# RPi-Display_v10.net
KiCad netlist of a schematic drawn in EAGLE
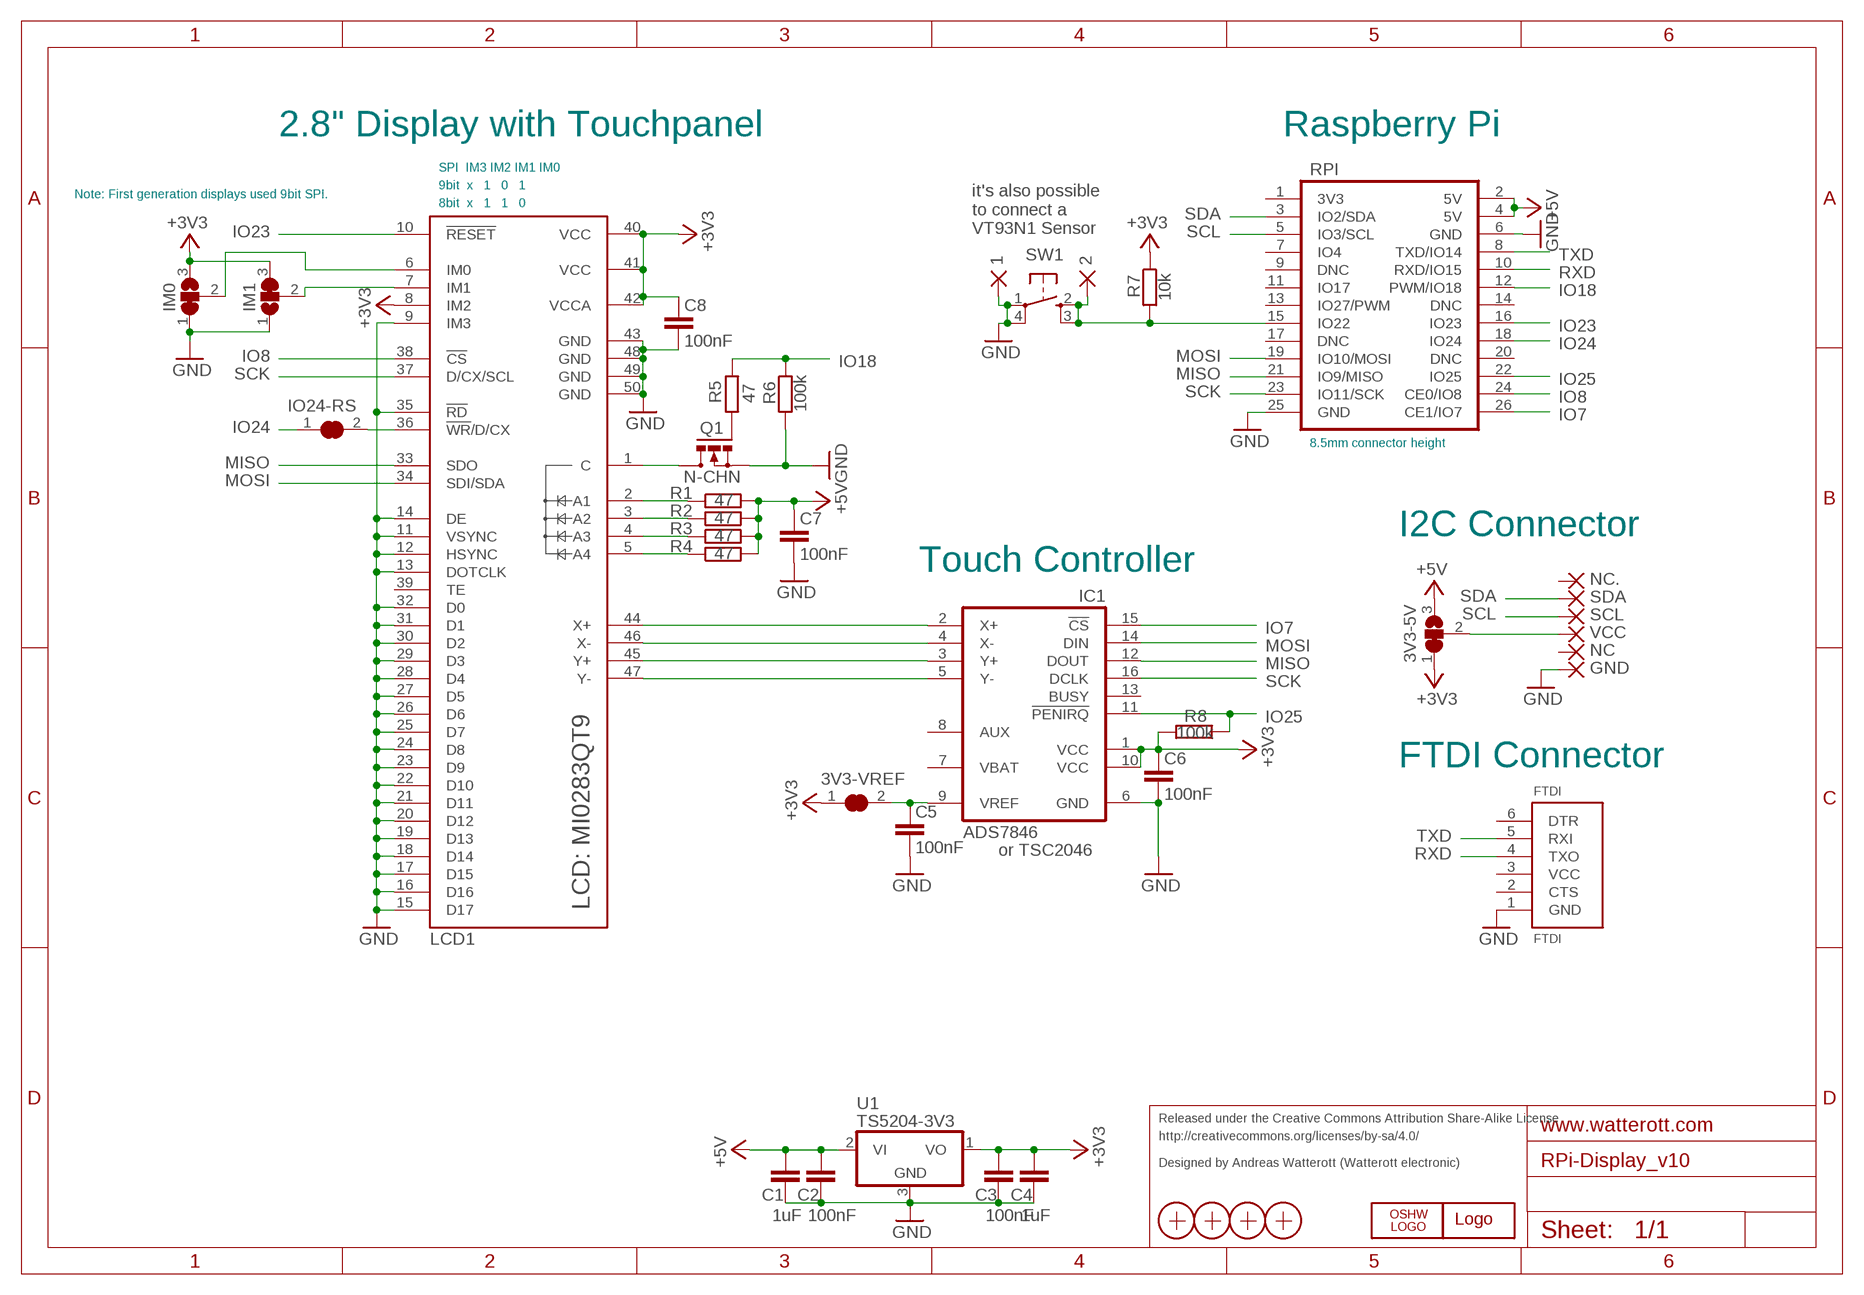
[diagram p0: schematic, sheet 1]

(export (version "E")
  (design (tool "Eeschema 10.0.6"))
  (components
    (comp (ref "1")
      (value "WIREPADSMD1,27-254")
      (footprint "eagle-import:SMD1,27-2,54")
      (libsource (lib "eagle-import") (part "WIREPADSMD1,27-254"))
    )
    (comp (ref "2")
      (value "WIREPADSMD1,27-254")
      (footprint "eagle-import:SMD1,27-2,54")
      (libsource (lib "eagle-import") (part "WIREPADSMD1,27-254"))
    )
    (comp (ref "3V3-5V")
      (value "SJ2W")
      (footprint "eagle-import:SJ_2")
      (libsource (lib "eagle-import") (part "SJ2W"))
    )
    (comp (ref "3V3-VREF")
      (value "SJ")
      (footprint "eagle-import:SJ")
      (libsource (lib "eagle-import") (part "SJ"))
    )
    (comp (ref "C1")
      (value "1uF")
      (footprint "eagle-import:C0603")
      (libsource (lib "eagle-import") (part "C-EUC0603"))
    )
    (comp (ref "C2")
      (value "100nF")
      (footprint "eagle-import:C0603")
      (libsource (lib "eagle-import") (part "C-EUC0603"))
    )
    (comp (ref "C3")
      (value "100nF")
      (footprint "eagle-import:C0603")
      (libsource (lib "eagle-import") (part "C-EUC0603"))
    )
    (comp (ref "C4")
      (value "1uF")
      (footprint "eagle-import:C0603")
      (libsource (lib "eagle-import") (part "C-EUC0603"))
    )
    (comp (ref "C5")
      (value "100nF")
      (footprint "eagle-import:C0603")
      (libsource (lib "eagle-import") (part "C-EUC0603"))
    )
    (comp (ref "C6")
      (value "100nF")
      (footprint "eagle-import:C0603")
      (libsource (lib "eagle-import") (part "C-EUC0603"))
    )
    (comp (ref "C7")
      (value "100nF")
      (footprint "eagle-import:C0603")
      (libsource (lib "eagle-import") (part "C-EUC0603"))
    )
    (comp (ref "C8")
      (value "100nF")
      (footprint "eagle-import:C0603")
      (libsource (lib "eagle-import") (part "C-EUC0603"))
    )
    (comp (ref "FTDI")
      (value "FTDI")
      (footprint "eagle-import:FTDI")
      (libsource (lib "eagle-import") (part "FTDI"))
    )
    (comp (ref "GND")
      (value "WIREPADSMD1,27-254")
      (footprint "eagle-import:SMD1,27-2,54")
      (libsource (lib "eagle-import") (part "WIREPADSMD1,27-254"))
    )
    (comp (ref "IC1")
      (value "ADS7846")
      (footprint "eagle-import:SSOP16")
      (libsource (lib "eagle-import") (part "ADS7846"))
    )
    (comp (ref "IM0")
      (value "SJ2W")
      (footprint "eagle-import:SJ_2")
      (libsource (lib "eagle-import") (part "SJ2W"))
    )
    (comp (ref "IM1")
      (value "SJ2W")
      (footprint "eagle-import:SJ_2")
      (libsource (lib "eagle-import") (part "SJ2W"))
    )
    (comp (ref "IO24-RS")
      (value "SJ")
      (footprint "eagle-import:SJ")
      (libsource (lib "eagle-import") (part "SJ"))
    )
    (comp (ref "LCD1")
      (value "MI0283QT9")
      (footprint "eagle-import:MI0283QT9")
      (libsource (lib "eagle-import") (part "MI0283QT9"))
    )
    (comp (ref "LOGO1")
      (value "OSHW_LOGO_6MILX0150-NT")
      (footprint "eagle-import:OSHW_6X150_NOTEXT")
      (libsource (lib "eagle-import") (part "OSHW_LOGO_6MILX0150-NT"))
    )
    (comp (ref "NC")
      (value "WIREPADSMD1,27-254")
      (footprint "eagle-import:SMD1,27-2,54")
      (libsource (lib "eagle-import") (part "WIREPADSMD1,27-254"))
    )
    (comp (ref "NC.")
      (value "WIREPADSMD1,27-254")
      (footprint "eagle-import:SMD1,27-2,54")
      (libsource (lib "eagle-import") (part "WIREPADSMD1,27-254"))
    )
    (comp (ref "Q1")
      (value "N-CHN")
      (footprint "eagle-import:MICRO3")
      (libsource (lib "eagle-import") (part "IRLML2502"))
    )
    (comp (ref "R1")
      (value "47")
      (footprint "eagle-import:R0603")
      (libsource (lib "eagle-import") (part "R-EU_R0603"))
    )
    (comp (ref "R2")
      (value "47")
      (footprint "eagle-import:R0603")
      (libsource (lib "eagle-import") (part "R-EU_R0603"))
    )
    (comp (ref "R3")
      (value "47")
      (footprint "eagle-import:R0603")
      (libsource (lib "eagle-import") (part "R-EU_R0603"))
    )
    (comp (ref "R4")
      (value "47")
      (footprint "eagle-import:R0603")
      (libsource (lib "eagle-import") (part "R-EU_R0603"))
    )
    (comp (ref "R5")
      (value "47")
      (footprint "eagle-import:R0603")
      (libsource (lib "eagle-import") (part "R-EU_R0603"))
    )
    (comp (ref "R6")
      (value "100k")
      (footprint "eagle-import:R0603")
      (libsource (lib "eagle-import") (part "R-EU_R0603"))
    )
    (comp (ref "R7")
      (value "10k")
      (footprint "eagle-import:R0603")
      (libsource (lib "eagle-import") (part "R-EU_R0603"))
    )
    (comp (ref "R8")
      (value "100k")
      (footprint "eagle-import:R0603")
      (libsource (lib "eagle-import") (part "R-EU_R0603"))
    )
    (comp (ref "RPI")
      (value "RPI")
      (footprint "eagle-import:RPI")
      (libsource (lib "eagle-import") (part "RPI"))
    )
    (comp (ref "SCL")
      (value "WIREPADSMD1,27-254")
      (footprint "eagle-import:SMD1,27-2,54")
      (libsource (lib "eagle-import") (part "WIREPADSMD1,27-254"))
    )
    (comp (ref "SDA")
      (value "WIREPADSMD1,27-254")
      (footprint "eagle-import:SMD1,27-2,54")
      (libsource (lib "eagle-import") (part "WIREPADSMD1,27-254"))
    )
    (comp (ref "SW1")
      (value "SW4S")
      (footprint "eagle-import:SW_SMD4")
      (libsource (lib "eagle-import") (part "SW4S"))
    )
    (comp (ref "U$1")
      (value "WE-LOGO")
      (footprint "eagle-import:WE-LOGO")
      (libsource (lib "eagle-import") (part "WE-LOGOPLACE"))
    )
    (comp (ref "U1")
      (value "TS5204-3V3")
      (footprint "eagle-import:SOT23")
      (libsource (lib "eagle-import") (part "TS5204"))
    )
    (comp (ref "VCC")
      (value "WIREPADSMD1,27-254")
      (footprint "eagle-import:SMD1,27-2,54")
      (libsource (lib "eagle-import") (part "WIREPADSMD1,27-254"))
    )
    (comp (ref "X1")
      (value "PASSER")
      (footprint "eagle-import:PASSER")
      (libsource (lib "eagle-import") (part "PASSER"))
    )
    (comp (ref "X2")
      (value "PASSER")
      (footprint "eagle-import:PASSER")
      (libsource (lib "eagle-import") (part "PASSER"))
    )
    (comp (ref "X3")
      (value "PASSER")
      (footprint "eagle-import:PASSER")
      (libsource (lib "eagle-import") (part "PASSER"))
    )
    (comp (ref "X4")
      (value "PASSER")
      (footprint "eagle-import:PASSER")
      (libsource (lib "eagle-import") (part "PASSER"))
    )
  )
  (nets
    (net (code "1") (name "+3V3") (class "Default")
      (node (ref "3V3-5V") (pin "1") (pinfunction "1_1") (pintype "passive"))
      (node (ref "3V3-VREF") (pin "1") (pinfunction "1_1") (pintype "passive"))
      (node (ref "C3") (pin "1") (pinfunction "1_1") (pintype "passive"))
      (node (ref "C4") (pin "1") (pinfunction "1_1") (pintype "passive"))
      (node (ref "C6") (pin "1") (pinfunction "1_1") (pintype "passive"))
      (node (ref "C8") (pin "1") (pinfunction "1_1") (pintype "passive"))
      (node (ref "IC1") (pin "1") (pinfunction "VCC_1") (pintype "power_in"))
      (node (ref "IC1") (pin "10") (pinfunction "VCC_10") (pintype "power_in"))
      (node (ref "IM0") (pin "3") (pinfunction "3_3") (pintype "passive"))
      (node (ref "IM1") (pin "3") (pinfunction "3_3") (pintype "passive"))
      (node (ref "LCD1") (pin "40") (pinfunction "VCC_40") (pintype "power_in"))
      (node (ref "LCD1") (pin "41") (pinfunction "VCC_41") (pintype "power_in"))
      (node (ref "LCD1") (pin "42") (pinfunction "VCCA_42") (pintype "power_in"))
      (node (ref "LCD1") (pin "8") (pinfunction "IM2_8") (pintype "input"))
      (node (ref "R7") (pin "1") (pinfunction "1_1") (pintype "passive"))
      (node (ref "R8") (pin "2") (pinfunction "2_2") (pintype "passive"))
      (node (ref "U1") (pin "1") (pinfunction "VO_1") (pintype "passive"))
    )
    (net (code "2") (name "+5V") (class "Default")
      (node (ref "3V3-5V") (pin "3") (pinfunction "3_3") (pintype "passive"))
      (node (ref "C1") (pin "1") (pinfunction "1_1") (pintype "passive"))
      (node (ref "C2") (pin "1") (pinfunction "1_1") (pintype "passive"))
      (node (ref "C7") (pin "1") (pinfunction "1_1") (pintype "passive"))
      (node (ref "R1") (pin "2") (pinfunction "2_2") (pintype "passive"))
      (node (ref "R2") (pin "2") (pinfunction "2_2") (pintype "passive"))
      (node (ref "R3") (pin "2") (pinfunction "2_2") (pintype "passive"))
      (node (ref "R4") (pin "2") (pinfunction "2_2") (pintype "passive"))
      (node (ref "RPI") (pin "2") (pinfunction "5V_2") (pintype "passive"))
      (node (ref "RPI") (pin "4") (pinfunction "5V_4") (pintype "passive"))
      (node (ref "U1") (pin "2") (pinfunction "VI_2") (pintype "input"))
    )
    (net (code "3") (name "/IO7") (class "Default")
      (node (ref "IC1") (pin "15") (pinfunction "~{CS}_15") (pintype "input"))
      (node (ref "RPI") (pin "26") (pinfunction "CE1/IO7_26") (pintype "passive"))
    )
    (net (code "4") (name "/IO8") (class "Default")
      (node (ref "LCD1") (pin "38") (pinfunction "~{CS}_38") (pintype "input"))
      (node (ref "RPI") (pin "24") (pinfunction "CE0/IO8_24") (pintype "passive"))
    )
    (net (code "5") (name "/IO18") (class "Default")
      (node (ref "R5") (pin "2") (pinfunction "2_2") (pintype "passive"))
      (node (ref "R6") (pin "1") (pinfunction "1_1") (pintype "passive"))
      (node (ref "RPI") (pin "12") (pinfunction "PWM/IO18_12") (pintype "passive"))
    )
    (net (code "6") (name "/IO23") (class "Default")
      (node (ref "LCD1") (pin "10") (pinfunction "~{RESET}_10") (pintype "input"))
      (node (ref "RPI") (pin "16") (pinfunction "IO23_16") (pintype "passive"))
    )
    (net (code "7") (name "/IO24") (class "Default")
      (node (ref "IO24-RS") (pin "1") (pinfunction "1_1") (pintype "passive"))
      (node (ref "RPI") (pin "18") (pinfunction "IO24_18") (pintype "passive"))
    )
    (net (code "8") (name "/IO25") (class "Default")
      (node (ref "IC1") (pin "11") (pinfunction "~{PENIRQ}_11") (pintype "output"))
      (node (ref "R8") (pin "1") (pinfunction "1_1") (pintype "passive"))
      (node (ref "RPI") (pin "22") (pinfunction "IO25_22") (pintype "passive"))
    )
    (net (code "9") (name "/MISO") (class "Default")
      (node (ref "IC1") (pin "12") (pinfunction "DOUT_12") (pintype "input"))
      (node (ref "LCD1") (pin "33") (pinfunction "SDO_33") (pintype "output"))
      (node (ref "RPI") (pin "21") (pinfunction "IO9/MISO_21") (pintype "passive"))
    )
    (net (code "10") (name "/MOSI") (class "Default")
      (node (ref "IC1") (pin "14") (pinfunction "DIN_14") (pintype "input"))
      (node (ref "LCD1") (pin "34") (pinfunction "SDI/SDA_34") (pintype "input"))
      (node (ref "RPI") (pin "19") (pinfunction "IO10/MOSI_19") (pintype "passive"))
    )
    (net (code "11") (name "/RXD") (class "Default")
      (node (ref "FTDI") (pin "4") (pinfunction "TXO_4") (pintype "bidirectional"))
      (node (ref "RPI") (pin "10") (pinfunction "RXD/IO15_10") (pintype "passive"))
    )
    (net (code "12") (name "/SCK") (class "Default")
      (node (ref "IC1") (pin "16") (pinfunction "DCLK_16") (pintype "output"))
      (node (ref "LCD1") (pin "37") (pinfunction "D/CX/SCL_37") (pintype "input"))
      (node (ref "RPI") (pin "23") (pinfunction "IO11/SCK_23") (pintype "passive"))
    )
    (net (code "13") (name "/SCL") (class "Default")
      (node (ref "RPI") (pin "5") (pinfunction "IO3/SCL_5") (pintype "passive"))
      (node (ref "SCL") (pin "1") (pinfunction "P_1") (pintype "passive"))
    )
    (net (code "14") (name "/SDA") (class "Default")
      (node (ref "RPI") (pin "3") (pinfunction "IO2/SDA_3") (pintype "passive"))
      (node (ref "SDA") (pin "1") (pinfunction "P_1") (pintype "passive"))
    )
    (net (code "15") (name "/TXD") (class "Default")
      (node (ref "FTDI") (pin "5") (pinfunction "RXI_5") (pintype "bidirectional"))
      (node (ref "RPI") (pin "8") (pinfunction "TXD/IO14_8") (pintype "passive"))
    )
    (net (code "16") (name "GND") (class "Default")
      (node (ref "1") (pin "1") (pinfunction "P_1") (pintype "passive"))
      (node (ref "C1") (pin "2") (pinfunction "2_2") (pintype "passive"))
      (node (ref "C2") (pin "2") (pinfunction "2_2") (pintype "passive"))
      (node (ref "C3") (pin "2") (pinfunction "2_2") (pintype "passive"))
      (node (ref "C4") (pin "2") (pinfunction "2_2") (pintype "passive"))
      (node (ref "C5") (pin "2") (pinfunction "2_2") (pintype "passive"))
      (node (ref "C6") (pin "2") (pinfunction "2_2") (pintype "passive"))
      (node (ref "C7") (pin "2") (pinfunction "2_2") (pintype "passive"))
      (node (ref "C8") (pin "2") (pinfunction "2_2") (pintype "passive"))
      (node (ref "FTDI") (pin "1") (pinfunction "GND_1") (pintype "bidirectional"))
      (node (ref "GND") (pin "1") (pinfunction "P_1") (pintype "passive"))
      (node (ref "IC1") (pin "6") (pinfunction "GND_6") (pintype "power_in"))
      (node (ref "IM0") (pin "1") (pinfunction "1_1") (pintype "passive"))
      (node (ref "IM1") (pin "1") (pinfunction "1_1") (pintype "passive"))
      (node (ref "LCD1") (pin "11") (pinfunction "VSYNC_11") (pintype "input"))
      (node (ref "LCD1") (pin "12") (pinfunction "HSYNC_12") (pintype "input"))
      (node (ref "LCD1") (pin "13") (pinfunction "DOTCLK_13") (pintype "input"))
      (node (ref "LCD1") (pin "14") (pinfunction "DE_14") (pintype "input"))
      (node (ref "LCD1") (pin "15") (pinfunction "D17_15") (pintype "input"))
      (node (ref "LCD1") (pin "16") (pinfunction "D16_16") (pintype "input"))
      (node (ref "LCD1") (pin "17") (pinfunction "D15_17") (pintype "input"))
      (node (ref "LCD1") (pin "18") (pinfunction "D14_18") (pintype "input"))
      (node (ref "LCD1") (pin "19") (pinfunction "D13_19") (pintype "input"))
      (node (ref "LCD1") (pin "20") (pinfunction "D12_20") (pintype "input"))
      (node (ref "LCD1") (pin "21") (pinfunction "D11_21") (pintype "input"))
      (node (ref "LCD1") (pin "22") (pinfunction "D10_22") (pintype "input"))
      (node (ref "LCD1") (pin "23") (pinfunction "D9_23") (pintype "input"))
      (node (ref "LCD1") (pin "24") (pinfunction "D8_24") (pintype "input"))
      (node (ref "LCD1") (pin "25") (pinfunction "D7_25") (pintype "input"))
      (node (ref "LCD1") (pin "26") (pinfunction "D6_26") (pintype "input"))
      (node (ref "LCD1") (pin "27") (pinfunction "D5_27") (pintype "input"))
      (node (ref "LCD1") (pin "28") (pinfunction "D4_28") (pintype "input"))
      (node (ref "LCD1") (pin "29") (pinfunction "D3_29") (pintype "input"))
      (node (ref "LCD1") (pin "30") (pinfunction "D2_30") (pintype "input"))
      (node (ref "LCD1") (pin "31") (pinfunction "D1_31") (pintype "input"))
      (node (ref "LCD1") (pin "32") (pinfunction "D0_32") (pintype "input"))
      (node (ref "LCD1") (pin "35") (pinfunction "~{RD}_35") (pintype "input"))
      (node (ref "LCD1") (pin "43") (pinfunction "GND_43") (pintype "power_in"))
      (node (ref "LCD1") (pin "48") (pinfunction "GND_48") (pintype "power_in"))
      (node (ref "LCD1") (pin "49") (pinfunction "GND_49") (pintype "power_in"))
      (node (ref "LCD1") (pin "50") (pinfunction "GND_50") (pintype "power_in"))
      (node (ref "LCD1") (pin "9") (pinfunction "IM3_9") (pintype "input"))
      (node (ref "Q1") (pin "2") (pinfunction "S_2") (pintype "passive"))
      (node (ref "R6") (pin "2") (pinfunction "2_2") (pintype "passive"))
      (node (ref "RPI") (pin "25") (pinfunction "GND_25") (pintype "passive"))
      (node (ref "RPI") (pin "6") (pinfunction "GND_6") (pintype "passive"))
      (node (ref "SW1") (pin "1") (pinfunction "P_1") (pintype "passive"))
      (node (ref "SW1") (pin "4") (pinfunction "P1_4") (pintype "passive"))
      (node (ref "U1") (pin "3") (pinfunction "GND_3") (pintype "passive"))
    )
    (net (code "17") (name "Net-(2-P)") (class "Default")
      (node (ref "2") (pin "1") (pinfunction "P_1") (pintype "passive"))
      (node (ref "R7") (pin "2") (pinfunction "2_2") (pintype "passive"))
      (node (ref "RPI") (pin "15") (pinfunction "IO22_15") (pintype "passive"))
      (node (ref "SW1") (pin "2") (pinfunction "S_2") (pintype "passive"))
      (node (ref "SW1") (pin "3") (pinfunction "S1_3") (pintype "passive"))
    )
    (net (code "18") (name "Net-(IC1-VREF)") (class "Default")
      (node (ref "3V3-VREF") (pin "2") (pinfunction "2_2") (pintype "passive"))
      (node (ref "C5") (pin "1") (pinfunction "1_1") (pintype "passive"))
      (node (ref "IC1") (pin "9") (pinfunction "VREF_9") (pintype "bidirectional"))
    )
    (net (code "19") (name "Net-(IC1-X+)") (class "Default")
      (node (ref "IC1") (pin "2") (pinfunction "X+_2") (pintype "input"))
      (node (ref "LCD1") (pin "44") (pinfunction "X+_44") (pintype "passive"))
    )
    (net (code "20") (name "Net-(IC1-X-)") (class "Default")
      (node (ref "IC1") (pin "4") (pinfunction "X-_4") (pintype "input"))
      (node (ref "LCD1") (pin "46") (pinfunction "X-_46") (pintype "passive"))
    )
    (net (code "21") (name "Net-(IC1-Y+)") (class "Default")
      (node (ref "IC1") (pin "3") (pinfunction "Y+_3") (pintype "input"))
      (node (ref "LCD1") (pin "45") (pinfunction "Y+_45") (pintype "passive"))
    )
    (net (code "22") (name "Net-(IC1-Y-)") (class "Default")
      (node (ref "IC1") (pin "5") (pinfunction "Y-_5") (pintype "input"))
      (node (ref "LCD1") (pin "47") (pinfunction "Y-_47") (pintype "passive"))
    )
    (net (code "23") (name "Net-(LCD1-A1)") (class "Default")
      (node (ref "LCD1") (pin "2") (pinfunction "A1_2") (pintype "power_in"))
      (node (ref "R1") (pin "1") (pinfunction "1_1") (pintype "passive"))
    )
    (net (code "24") (name "Net-(LCD1-A2)") (class "Default")
      (node (ref "LCD1") (pin "3") (pinfunction "A2_3") (pintype "power_in"))
      (node (ref "R2") (pin "1") (pinfunction "1_1") (pintype "passive"))
    )
    (net (code "25") (name "Net-(LCD1-A3)") (class "Default")
      (node (ref "LCD1") (pin "4") (pinfunction "A3_4") (pintype "power_in"))
      (node (ref "R3") (pin "1") (pinfunction "1_1") (pintype "passive"))
    )
    (net (code "26") (name "Net-(LCD1-A4)") (class "Default")
      (node (ref "LCD1") (pin "5") (pinfunction "A4_5") (pintype "power_in"))
      (node (ref "R4") (pin "1") (pinfunction "1_1") (pintype "passive"))
    )
    (net (code "27") (name "Net-(LCD1-C)") (class "Default")
      (node (ref "LCD1") (pin "1") (pinfunction "C_1") (pintype "power_in"))
      (node (ref "Q1") (pin "3") (pinfunction "D_3") (pintype "passive"))
    )
    (net (code "28") (name "Net-(LCD1-IM0)") (class "Default")
      (node (ref "IM0") (pin "2") (pinfunction "2_2") (pintype "passive"))
      (node (ref "LCD1") (pin "6") (pinfunction "IM0_6") (pintype "input"))
    )
    (net (code "29") (name "Net-(LCD1-IM1)") (class "Default")
      (node (ref "IM1") (pin "2") (pinfunction "2_2") (pintype "passive"))
      (node (ref "LCD1") (pin "7") (pinfunction "IM1_7") (pintype "input"))
    )
    (net (code "30") (name "Net-(LCD1-~{WR}{slash}D{slash}CX)") (class "Default")
      (node (ref "IO24-RS") (pin "2") (pinfunction "2_2") (pintype "passive"))
      (node (ref "LCD1") (pin "36") (pinfunction "~{WR}/D/CX_36") (pintype "input"))
    )
    (net (code "31") (name "Net-(Q1-G)") (class "Default")
      (node (ref "Q1") (pin "1") (pinfunction "G_1") (pintype "passive"))
      (node (ref "R5") (pin "1") (pinfunction "1_1") (pintype "passive"))
    )
    (net (code "32") (name "Net-(VCC-P)") (class "Default")
      (node (ref "3V3-5V") (pin "2") (pinfunction "2_2") (pintype "passive"))
      (node (ref "VCC") (pin "1") (pinfunction "P_1") (pintype "passive"))
    )
    (net (code "33") (name "unconnected-(FTDI-CTS-Pad2)") (class "Default")
      (node (ref "FTDI") (pin "2") (pinfunction "CTS_2") (pintype "bidirectional"))
    )
    (net (code "34") (name "unconnected-(FTDI-DTR-Pad6)") (class "Default")
      (node (ref "FTDI") (pin "6") (pinfunction "DTR_6") (pintype "bidirectional"))
    )
    (net (code "35") (name "unconnected-(FTDI-VCC-Pad3)") (class "Default")
      (node (ref "FTDI") (pin "3") (pinfunction "VCC_3") (pintype "bidirectional"))
    )
    (net (code "36") (name "unconnected-(IC1-AUX-Pad8)") (class "Default")
      (node (ref "IC1") (pin "8") (pinfunction "AUX_8") (pintype "input"))
    )
    (net (code "37") (name "unconnected-(IC1-BUSY-Pad13)") (class "Default")
      (node (ref "IC1") (pin "13") (pinfunction "BUSY_13") (pintype "output"))
    )
    (net (code "38") (name "unconnected-(IC1-VBAT-Pad7)") (class "Default")
      (node (ref "IC1") (pin "7") (pinfunction "VBAT_7") (pintype "input"))
    )
    (net (code "39") (name "unconnected-(LCD1-TE-Pad39)") (class "Default")
      (node (ref "LCD1") (pin "39") (pinfunction "TE_39") (pintype "output"))
    )
    (net (code "40") (name "unconnected-(NC-P-Pad1)") (class "Default")
      (node (ref "NC") (pin "1") (pinfunction "P_1") (pintype "passive"))
    )
    (net (code "41") (name "unconnected-(NC.-P-Pad1)") (class "Default")
      (node (ref "NC.") (pin "1") (pinfunction "P_1") (pintype "passive"))
    )
    (net (code "42") (name "unconnected-(RPI-3V3-Pad1)") (class "Default")
      (node (ref "RPI") (pin "1") (pinfunction "3V3_1") (pintype "passive"))
    )
    (net (code "43") (name "unconnected-(RPI-DNC-Pad9)") (class "Default")
      (node (ref "RPI") (pin "9") (pinfunction "DNC_9") (pintype "passive"))
    )
    (net (code "44") (name "unconnected-(RPI-DNC-Pad14)") (class "Default")
      (node (ref "RPI") (pin "14") (pinfunction "DNC_14") (pintype "passive"))
    )
    (net (code "45") (name "unconnected-(RPI-DNC-Pad17)") (class "Default")
      (node (ref "RPI") (pin "17") (pinfunction "DNC_17") (pintype "passive"))
    )
    (net (code "46") (name "unconnected-(RPI-DNC-Pad20)") (class "Default")
      (node (ref "RPI") (pin "20") (pinfunction "DNC_20") (pintype "passive"))
    )
    (net (code "47") (name "unconnected-(RPI-IO4-Pad7)") (class "Default")
      (node (ref "RPI") (pin "7") (pinfunction "IO4_7") (pintype "passive"))
    )
    (net (code "48") (name "unconnected-(RPI-IO17-Pad11)") (class "Default")
      (node (ref "RPI") (pin "11") (pinfunction "IO17_11") (pintype "passive"))
    )
    (net (code "49") (name "unconnected-(RPI-IO27{slash}PWM-Pad13)") (class "Default")
      (node (ref "RPI") (pin "13") (pinfunction "IO27/PWM_13") (pintype "passive"))
    )
  )
)
